# expansion.net
KiCad netlist of a schematic drawn in EAGLE
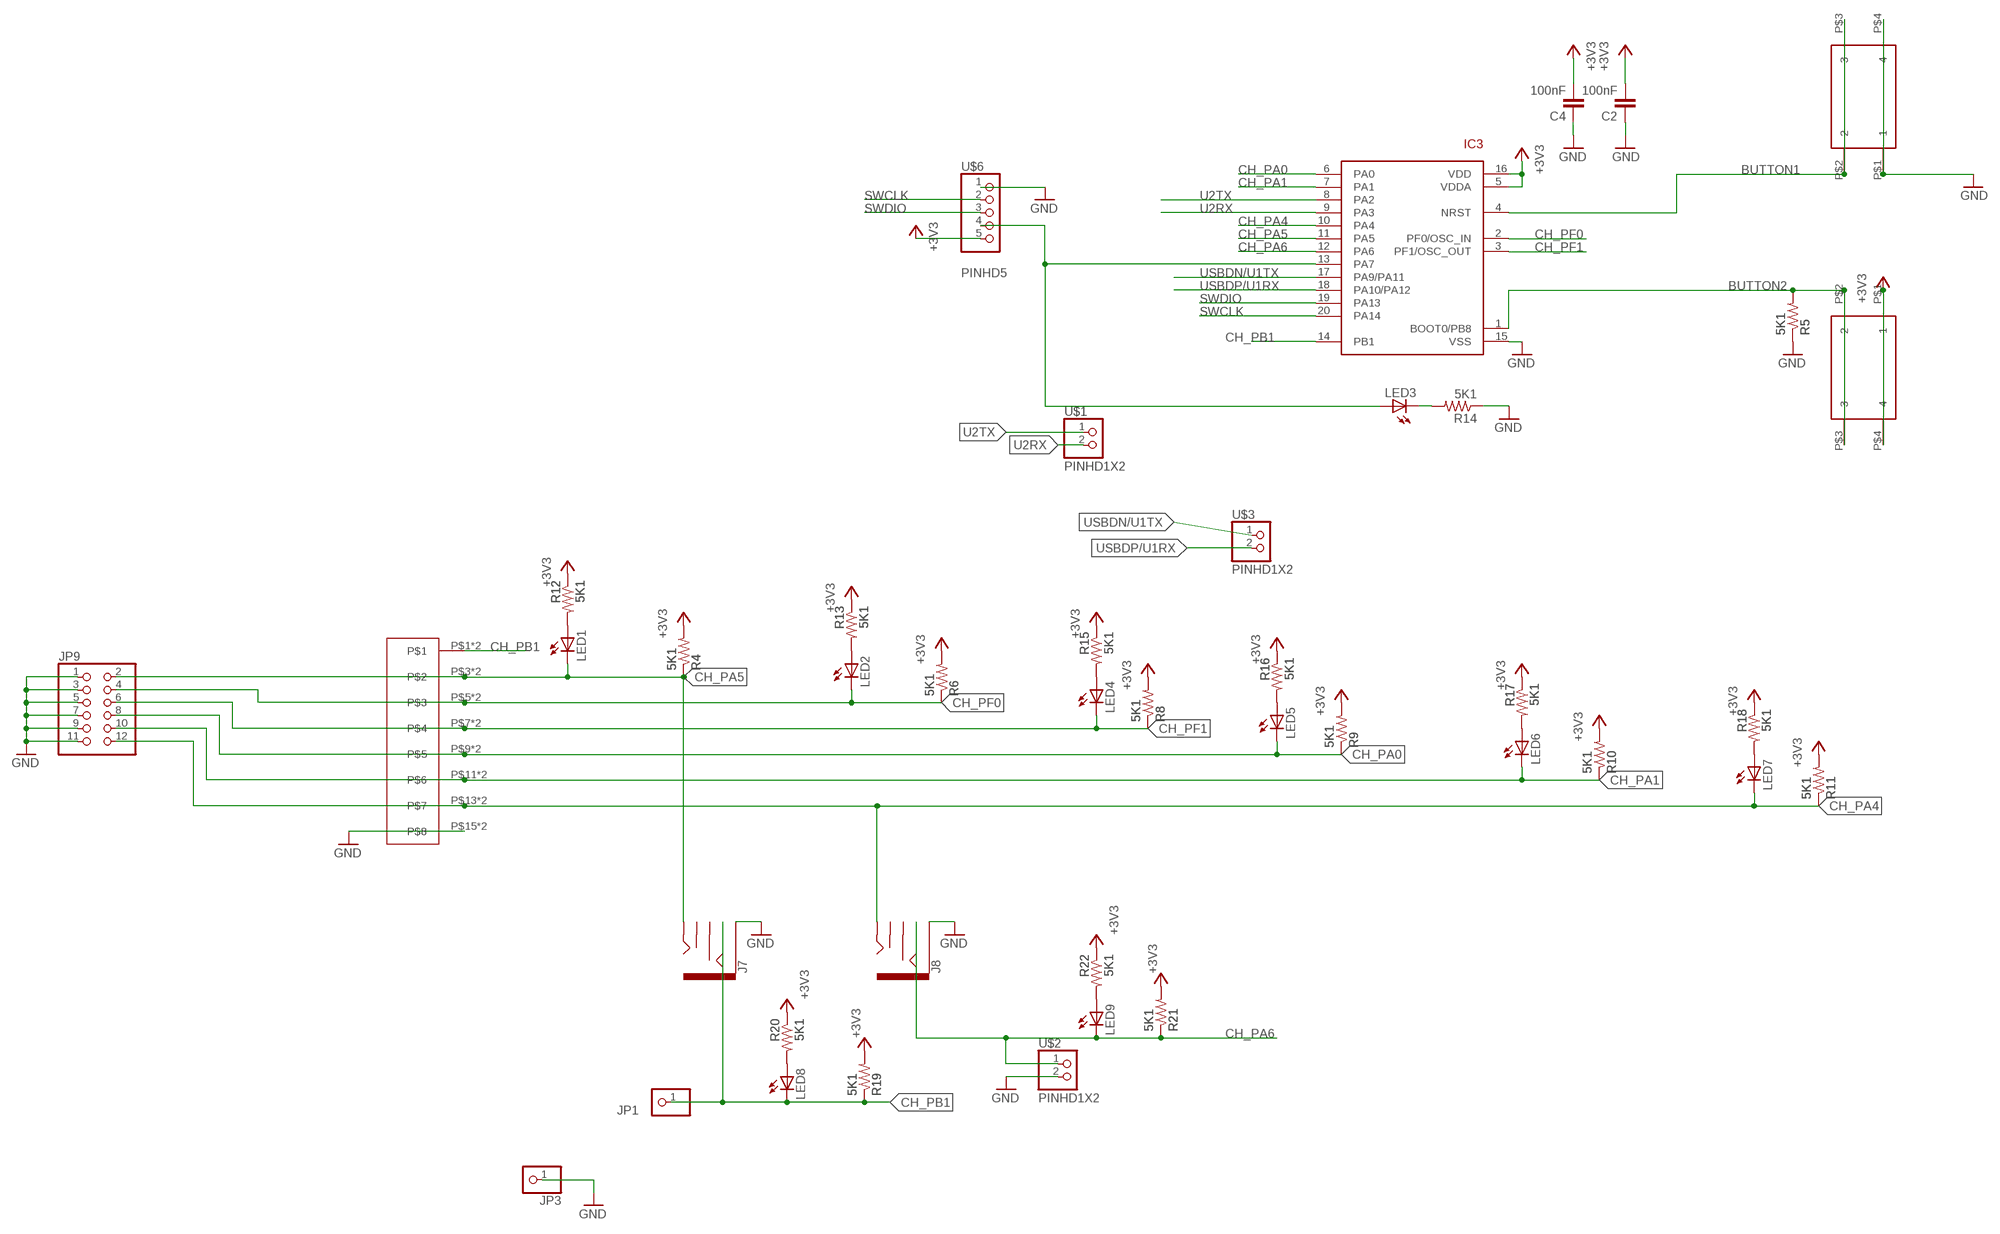
[diagram p0: schematic, sheet 1, part 1 of 2]
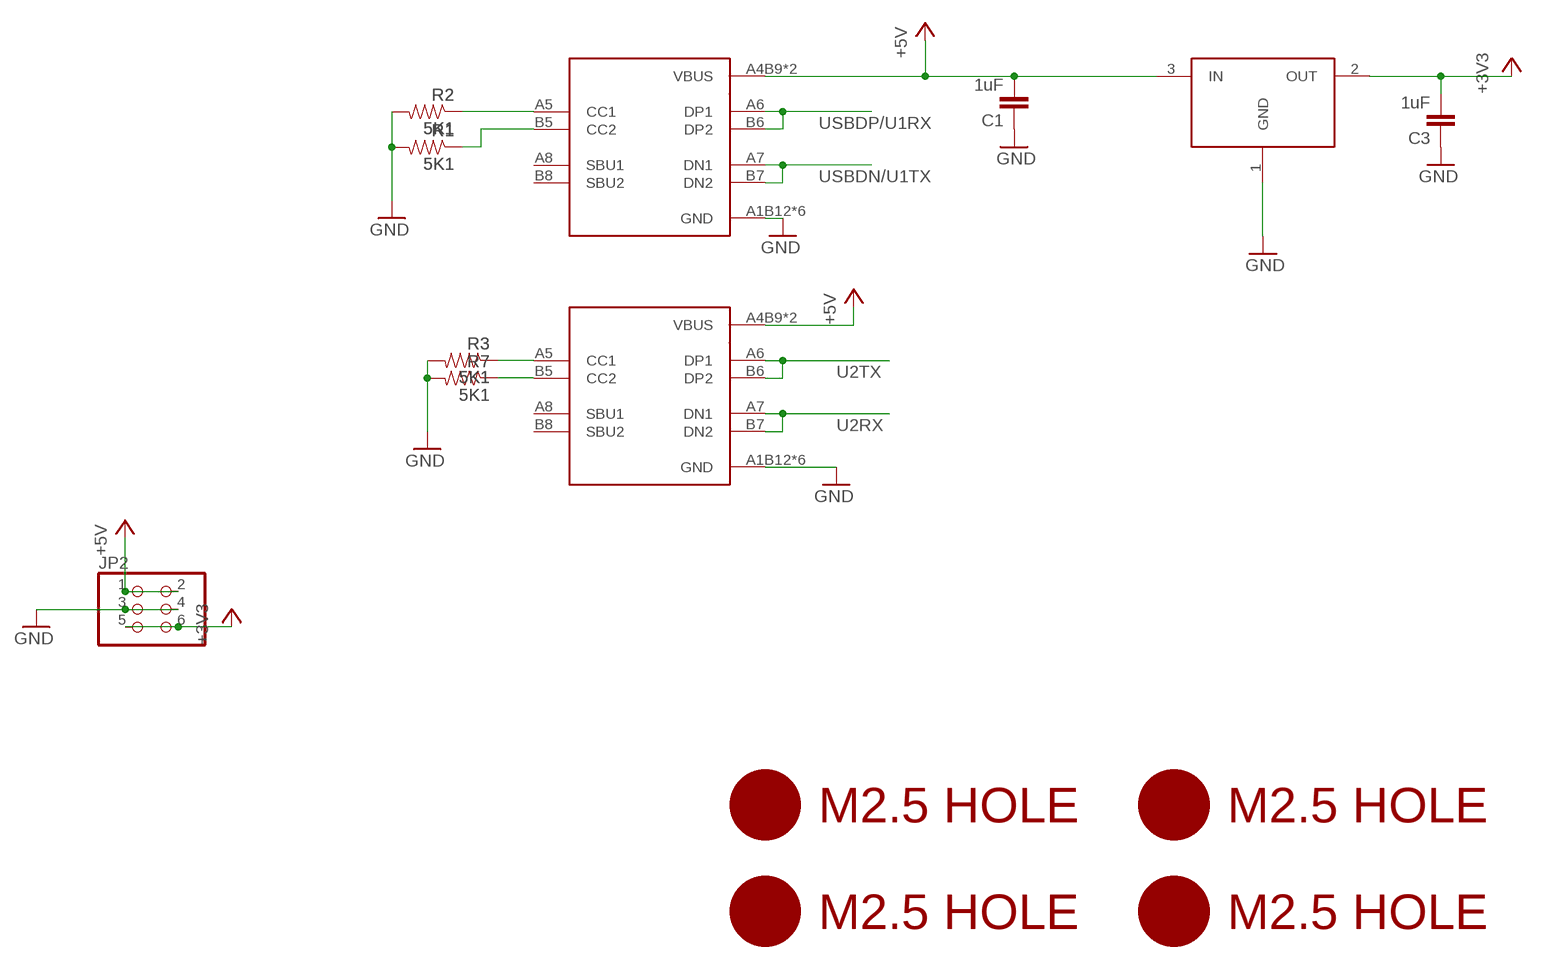
[diagram p1: schematic, sheet 1, part 2 of 2]

(export (version "E")
  (design (tool "Eeschema 10.0.6"))
  (components
    (comp (ref "C1")
      (value "1uF")
      (footprint "eagle-import:0805")
      (libsource (lib "eagle-import") (part "CAP0805"))
    )
    (comp (ref "C2")
      (value "100nF")
      (footprint "eagle-import:0805")
      (libsource (lib "eagle-import") (part "CAP0805"))
    )
    (comp (ref "C3")
      (value "1uF")
      (footprint "eagle-import:0805")
      (libsource (lib "eagle-import") (part "CAP0805"))
    )
    (comp (ref "C4")
      (value "100nF")
      (footprint "eagle-import:0805")
      (libsource (lib "eagle-import") (part "CAP0805"))
    )
    (comp (ref "IC3")
      (value "STM32F042F4")
      (footprint "eagle-import:TSSOP20")
      (libsource (lib "eagle-import") (part "STM32F042F4"))
    )
    (comp (ref "J7")
      (value "AUDIO_JACK_3.5MM_PTH")
      (footprint "eagle-import:AUDIO-JACK")
      (libsource (lib "eagle-import") (part "AUDIO_JACK_3.5MM_PTH"))
    )
    (comp (ref "J8")
      (value "AUDIO_JACK_3.5MM_PTH")
      (footprint "eagle-import:AUDIO-JACK")
      (libsource (lib "eagle-import") (part "AUDIO_JACK_3.5MM_PTH"))
    )
    (comp (ref "JP1")
      (value "PINHD-1X1")
      (footprint "eagle-import:1X01")
      (libsource (lib "eagle-import") (part "PINHD-1X1"))
    )
    (comp (ref "JP2")
      (value "PINHD-2X3")
      (footprint "eagle-import:2X03")
      (libsource (lib "eagle-import") (part "PINHD-2X3"))
    )
    (comp (ref "JP3")
      (value "PINHD-1X1")
      (footprint "eagle-import:1X01")
      (libsource (lib "eagle-import") (part "PINHD-1X1"))
    )
    (comp (ref "JP9")
      (value "PINHD-2X6")
      (footprint "eagle-import:2X06")
      (libsource (lib "eagle-import") (part "PINHD-2X6"))
    )
    (comp (ref "LED1")
      (value "LEDCHIP-LED0805")
      (footprint "eagle-import:CHIP-LED0805")
      (libsource (lib "eagle-import") (part "LEDCHIP-LED0805"))
    )
    (comp (ref "LED2")
      (value "LEDCHIP-LED0805")
      (footprint "eagle-import:CHIP-LED0805")
      (libsource (lib "eagle-import") (part "LEDCHIP-LED0805"))
    )
    (comp (ref "LED3")
      (value "LEDCHIP-LED0805")
      (footprint "eagle-import:CHIP-LED0805")
      (libsource (lib "eagle-import") (part "LEDCHIP-LED0805"))
    )
    (comp (ref "LED4")
      (value "LEDCHIP-LED0805")
      (footprint "eagle-import:CHIP-LED0805")
      (libsource (lib "eagle-import") (part "LEDCHIP-LED0805"))
    )
    (comp (ref "LED5")
      (value "LEDCHIP-LED0805")
      (footprint "eagle-import:CHIP-LED0805")
      (libsource (lib "eagle-import") (part "LEDCHIP-LED0805"))
    )
    (comp (ref "LED6")
      (value "LEDCHIP-LED0805")
      (footprint "eagle-import:CHIP-LED0805")
      (libsource (lib "eagle-import") (part "LEDCHIP-LED0805"))
    )
    (comp (ref "LED7")
      (value "LEDCHIP-LED0805")
      (footprint "eagle-import:CHIP-LED0805")
      (libsource (lib "eagle-import") (part "LEDCHIP-LED0805"))
    )
    (comp (ref "LED8")
      (value "LEDCHIP-LED0805")
      (footprint "eagle-import:CHIP-LED0805")
      (libsource (lib "eagle-import") (part "LEDCHIP-LED0805"))
    )
    (comp (ref "LED9")
      (value "LEDCHIP-LED0805")
      (footprint "eagle-import:CHIP-LED0805")
      (libsource (lib "eagle-import") (part "LEDCHIP-LED0805"))
    )
    (comp (ref "R1")
      (value "5K1")
      (footprint "eagle-import:0805")
      (libsource (lib "eagle-import") (part "joyAnalog_RESISTOR0805-RES"))
    )
    (comp (ref "R2")
      (value "5K1")
      (footprint "eagle-import:0805")
      (libsource (lib "eagle-import") (part "joyAnalog_RESISTOR0805-RES"))
    )
    (comp (ref "R3")
      (value "5K1")
      (footprint "eagle-import:0805")
      (libsource (lib "eagle-import") (part "joyAnalog_RESISTOR0805-RES"))
    )
    (comp (ref "R4")
      (value "5K1")
      (footprint "eagle-import:0805")
      (libsource (lib "eagle-import") (part "joyAnalog_RESISTOR0805-RES"))
    )
    (comp (ref "R5")
      (value "5K1")
      (footprint "eagle-import:0805")
      (libsource (lib "eagle-import") (part "joyAnalog_RESISTOR0805-RES"))
    )
    (comp (ref "R6")
      (value "5K1")
      (footprint "eagle-import:0805")
      (libsource (lib "eagle-import") (part "joyAnalog_RESISTOR0805-RES"))
    )
    (comp (ref "R7")
      (value "5K1")
      (footprint "eagle-import:0805")
      (libsource (lib "eagle-import") (part "joyAnalog_RESISTOR0805-RES"))
    )
    (comp (ref "R8")
      (value "5K1")
      (footprint "eagle-import:0805")
      (libsource (lib "eagle-import") (part "joyAnalog_RESISTOR0805-RES"))
    )
    (comp (ref "R9")
      (value "5K1")
      (footprint "eagle-import:0805")
      (libsource (lib "eagle-import") (part "joyAnalog_RESISTOR0805-RES"))
    )
    (comp (ref "R10")
      (value "5K1")
      (footprint "eagle-import:0805")
      (libsource (lib "eagle-import") (part "joyAnalog_RESISTOR0805-RES"))
    )
    (comp (ref "R11")
      (value "5K1")
      (footprint "eagle-import:0805")
      (libsource (lib "eagle-import") (part "joyAnalog_RESISTOR0805-RES"))
    )
    (comp (ref "R12")
      (value "5K1")
      (footprint "eagle-import:0805")
      (libsource (lib "eagle-import") (part "joyAnalog_RESISTOR0805-RES"))
    )
    (comp (ref "R13")
      (value "5K1")
      (footprint "eagle-import:0805")
      (libsource (lib "eagle-import") (part "joyAnalog_RESISTOR0805-RES"))
    )
    (comp (ref "R14")
      (value "5K1")
      (footprint "eagle-import:0805")
      (libsource (lib "eagle-import") (part "RESISTOR0805-RES"))
    )
    (comp (ref "R15")
      (value "5K1")
      (footprint "eagle-import:0805")
      (libsource (lib "eagle-import") (part "joyAnalog_RESISTOR0805-RES"))
    )
    (comp (ref "R16")
      (value "5K1")
      (footprint "eagle-import:0805")
      (libsource (lib "eagle-import") (part "joyAnalog_RESISTOR0805-RES"))
    )
    (comp (ref "R17")
      (value "5K1")
      (footprint "eagle-import:0805")
      (libsource (lib "eagle-import") (part "joyAnalog_RESISTOR0805-RES"))
    )
    (comp (ref "R18")
      (value "5K1")
      (footprint "eagle-import:0805")
      (libsource (lib "eagle-import") (part "joyAnalog_RESISTOR0805-RES"))
    )
    (comp (ref "R19")
      (value "5K1")
      (footprint "eagle-import:0805")
      (libsource (lib "eagle-import") (part "joyAnalog_RESISTOR0805-RES"))
    )
    (comp (ref "R20")
      (value "5K1")
      (footprint "eagle-import:0805")
      (libsource (lib "eagle-import") (part "joyAnalog_RESISTOR0805-RES"))
    )
    (comp (ref "R21")
      (value "5K1")
      (footprint "eagle-import:0805")
      (libsource (lib "eagle-import") (part "joyAnalog_RESISTOR0805-RES"))
    )
    (comp (ref "R22")
      (value "5K1")
      (footprint "eagle-import:0805")
      (libsource (lib "eagle-import") (part "joyAnalog_RESISTOR0805-RES"))
    )
    (comp (ref "SW3")
      (value "324_SW")
      (footprint "eagle-import:342_SWICH_FOOT")
      (libsource (lib "eagle-import") (part "324_SW"))
    )
    (comp (ref "SW4")
      (value "324_SW")
      (footprint "eagle-import:342_SWICH_FOOT")
      (libsource (lib "eagle-import") (part "324_SW"))
    )
    (comp (ref "U$1")
      (value "PINHD1X2")
      (footprint "eagle-import:1X02")
      (libsource (lib "eagle-import") (part "PINHD1X2"))
    )
    (comp (ref "U$2")
      (value "PINHD1X2")
      (footprint "eagle-import:1X02")
      (libsource (lib "eagle-import") (part "PINHD1X2"))
    )
    (comp (ref "U$3")
      (value "PINHD1X2")
      (footprint "eagle-import:1X02")
      (libsource (lib "eagle-import") (part "PINHD1X2"))
    )
    (comp (ref "U$6")
      (value "PINHD5")
      (footprint "eagle-import:1X05")
      (libsource (lib "eagle-import") (part "PINHD5"))
    )
    (comp (ref "U$8")
      (value "M2.5HOLE")
      (footprint "eagle-import:M2.5HOLE")
      (libsource (lib "eagle-import") (part "M2.5HOLE"))
    )
    (comp (ref "U$9")
      (value "M2.5HOLE")
      (footprint "eagle-import:M2.5HOLE")
      (libsource (lib "eagle-import") (part "M2.5HOLE"))
    )
    (comp (ref "U$10")
      (value "M2.5HOLE")
      (footprint "eagle-import:M2.5HOLE")
      (libsource (lib "eagle-import") (part "M2.5HOLE"))
    )
    (comp (ref "U$11")
      (value "M2.5HOLE")
      (footprint "eagle-import:M2.5HOLE")
      (libsource (lib "eagle-import") (part "M2.5HOLE"))
    )
    (comp (ref "U$14")
      (value "DG2204R-5.0-8DG2204-8")
      (footprint "eagle-import:DG2204R-8")
      (libsource (lib "eagle-import") (part "DG2204R-5.0-8DG2204-8"))
    )
    (comp (ref "U1")
      (value "USBC_16P")
      (footprint "eagle-import:USBC_16P_FOOT")
      (libsource (lib "eagle-import") (part "USBC_16P"))
    )
    (comp (ref "U2")
      (value "USBC_16P")
      (footprint "eagle-import:USBC_16P_FOOT")
      (libsource (lib "eagle-import") (part "USBC_16P"))
    )
    (comp (ref "U4")
      (value "XC6206_DEV")
      (footprint "eagle-import:SOT23R_INFINEON")
      (libsource (lib "eagle-import") (part "XC6206_DEV"))
    )
  )
  (nets
    (net (code "1") (name "+3V3") (class "Default")
      (node (ref "C2") (pin "2") (pinfunction "2_2") (pintype "passive"))
      (node (ref "C3") (pin "2") (pinfunction "2_2") (pintype "passive"))
      (node (ref "C4") (pin "2") (pinfunction "2_2") (pintype "passive"))
      (node (ref "IC3") (pin "16") (pinfunction "VDD_16") (pintype "bidirectional"))
      (node (ref "IC3") (pin "5") (pinfunction "VDDA_5") (pintype "bidirectional"))
      (node (ref "JP2") (pin "5") (pinfunction "5_5") (pintype "passive"))
      (node (ref "JP2") (pin "6") (pinfunction "6_6") (pintype "passive"))
      (node (ref "R10") (pin "2") (pinfunction "2_2") (pintype "passive"))
      (node (ref "R11") (pin "2") (pinfunction "2_2") (pintype "passive"))
      (node (ref "R12") (pin "1") (pinfunction "1_1") (pintype "passive"))
      (node (ref "R13") (pin "1") (pinfunction "1_1") (pintype "passive"))
      (node (ref "R15") (pin "1") (pinfunction "1_1") (pintype "passive"))
      (node (ref "R16") (pin "1") (pinfunction "1_1") (pintype "passive"))
      (node (ref "R17") (pin "1") (pinfunction "1_1") (pintype "passive"))
      (node (ref "R18") (pin "1") (pinfunction "1_1") (pintype "passive"))
      (node (ref "R19") (pin "2") (pinfunction "2_2") (pintype "passive"))
      (node (ref "R20") (pin "1") (pinfunction "1_1") (pintype "passive"))
      (node (ref "R21") (pin "2") (pinfunction "2_2") (pintype "passive"))
      (node (ref "R22") (pin "1") (pinfunction "1_1") (pintype "passive"))
      (node (ref "R4") (pin "2") (pinfunction "2_2") (pintype "passive"))
      (node (ref "R6") (pin "2") (pinfunction "2_2") (pintype "passive"))
      (node (ref "R8") (pin "2") (pinfunction "2_2") (pintype "passive"))
      (node (ref "R9") (pin "2") (pinfunction "2_2") (pintype "passive"))
      (node (ref "SW4") (pin "P$1") (pinfunction "1_P$1") (pintype "bidirectional"))
      (node (ref "SW4") (pin "P$4") (pinfunction "4_P$4") (pintype "bidirectional"))
      (node (ref "U$6") (pin "5") (pinfunction "5_5") (pintype "passive"))
      (node (ref "U4") (pin "2") (pinfunction "OUT_2") (pintype "bidirectional"))
    )
    (net (code "2") (name "+5V") (class "Default")
      (node (ref "C1") (pin "2") (pinfunction "2_2") (pintype "passive"))
      (node (ref "JP2") (pin "1") (pinfunction "1_1") (pintype "passive"))
      (node (ref "JP2") (pin "2") (pinfunction "2_2") (pintype "passive"))
      (node (ref "U1") (pin "A4B9") (pinfunction "VBUS_A4B9") (pintype "bidirectional"))
      (node (ref "U1") (pin "B4A9") (pinfunction "VBUS_B4A9") (pintype "bidirectional"))
      (node (ref "U2") (pin "A4B9") (pinfunction "VBUS_A4B9") (pintype "bidirectional"))
      (node (ref "U2") (pin "B4A9") (pinfunction "VBUS_B4A9") (pintype "bidirectional"))
      (node (ref "U4") (pin "3") (pinfunction "IN_3") (pintype "bidirectional"))
    )
    (net (code "3") (name "/BUTTON1") (class "Default")
      (node (ref "IC3") (pin "4") (pinfunction "NRST_4") (pintype "bidirectional"))
      (node (ref "SW3") (pin "P$2") (pinfunction "2_P$2") (pintype "bidirectional"))
      (node (ref "SW3") (pin "P$3") (pinfunction "3_P$3") (pintype "bidirectional"))
    )
    (net (code "4") (name "/BUTTON2") (class "Default")
      (node (ref "IC3") (pin "1") (pinfunction "BOOT0/PB8_1") (pintype "bidirectional"))
      (node (ref "R5") (pin "2") (pinfunction "2_2") (pintype "passive"))
      (node (ref "SW4") (pin "P$2") (pinfunction "2_P$2") (pintype "bidirectional"))
      (node (ref "SW4") (pin "P$3") (pinfunction "3_P$3") (pintype "bidirectional"))
    )
    (net (code "5") (name "/CH_PA6") (class "Default")
      (node (ref "IC3") (pin "12") (pinfunction "PA6_12") (pintype "bidirectional"))
      (node (ref "J8") (pin "RING") (pinfunction "RING_RING") (pintype "bidirectional"))
      (node (ref "LED9") (pin "C") (pinfunction "C_C") (pintype "passive"))
      (node (ref "R21") (pin "1") (pinfunction "1_1") (pintype "passive"))
      (node (ref "U$2") (pin "1") (pinfunction "1_1") (pintype "passive"))
    )
    (net (code "6") (name "/SWCLK") (class "Default")
      (node (ref "IC3") (pin "20") (pinfunction "PA14_20") (pintype "bidirectional"))
      (node (ref "U$6") (pin "2") (pinfunction "2_2") (pintype "passive"))
    )
    (net (code "7") (name "/SWDIO") (class "Default")
      (node (ref "IC3") (pin "19") (pinfunction "PA13_19") (pintype "bidirectional"))
      (node (ref "U$6") (pin "3") (pinfunction "3_3") (pintype "passive"))
    )
    (net (code "8") (name "CH_PA0") (class "Default")
      (node (ref "IC3") (pin "6") (pinfunction "PA0_6") (pintype "bidirectional"))
      (node (ref "JP9") (pin "8") (pinfunction "8_8") (pintype "passive"))
      (node (ref "LED5") (pin "C") (pinfunction "C_C") (pintype "passive"))
      (node (ref "R9") (pin "1") (pinfunction "1_1") (pintype "passive"))
      (node (ref "U$14") (pin "P$10") (pinfunction "P$5_P$10") (pintype "bidirectional"))
      (node (ref "U$14") (pin "P$9") (pinfunction "P$5_P$9") (pintype "bidirectional"))
    )
    (net (code "9") (name "CH_PA1") (class "Default")
      (node (ref "IC3") (pin "7") (pinfunction "PA1_7") (pintype "bidirectional"))
      (node (ref "JP9") (pin "10") (pinfunction "10_10") (pintype "passive"))
      (node (ref "LED6") (pin "C") (pinfunction "C_C") (pintype "passive"))
      (node (ref "R10") (pin "1") (pinfunction "1_1") (pintype "passive"))
      (node (ref "U$14") (pin "P$11") (pinfunction "P$6_P$11") (pintype "bidirectional"))
      (node (ref "U$14") (pin "P$12") (pinfunction "P$6_P$12") (pintype "bidirectional"))
    )
    (net (code "10") (name "CH_PA4") (class "Default")
      (node (ref "IC3") (pin "10") (pinfunction "PA4_10") (pintype "bidirectional"))
      (node (ref "J8") (pin "TIP") (pinfunction "TIP_TIP") (pintype "bidirectional"))
      (node (ref "JP9") (pin "12") (pinfunction "12_12") (pintype "passive"))
      (node (ref "LED7") (pin "C") (pinfunction "C_C") (pintype "passive"))
      (node (ref "R11") (pin "1") (pinfunction "1_1") (pintype "passive"))
      (node (ref "U$14") (pin "P$13") (pinfunction "P$7_P$13") (pintype "bidirectional"))
      (node (ref "U$14") (pin "P$14") (pinfunction "P$7_P$14") (pintype "bidirectional"))
    )
    (net (code "11") (name "CH_PA5") (class "Default")
      (node (ref "IC3") (pin "11") (pinfunction "PA5_11") (pintype "bidirectional"))
      (node (ref "J7") (pin "TIP") (pinfunction "TIP_TIP") (pintype "bidirectional"))
      (node (ref "JP9") (pin "2") (pinfunction "2_2") (pintype "passive"))
      (node (ref "LED1") (pin "C") (pinfunction "C_C") (pintype "passive"))
      (node (ref "R4") (pin "1") (pinfunction "1_1") (pintype "passive"))
      (node (ref "U$14") (pin "P$3") (pinfunction "P$2_P$3") (pintype "bidirectional"))
      (node (ref "U$14") (pin "P$4") (pinfunction "P$2_P$4") (pintype "bidirectional"))
    )
    (net (code "12") (name "CH_PB1") (class "Default")
      (node (ref "IC3") (pin "14") (pinfunction "PB1_14") (pintype "bidirectional"))
      (node (ref "J7") (pin "RING") (pinfunction "RING_RING") (pintype "bidirectional"))
      (node (ref "JP1") (pin "1") (pinfunction "1_1") (pintype "passive"))
      (node (ref "LED8") (pin "C") (pinfunction "C_C") (pintype "passive"))
      (node (ref "R19") (pin "1") (pinfunction "1_1") (pintype "passive"))
      (node (ref "U$14") (pin "P$1") (pinfunction "P$1_P$1") (pintype "bidirectional"))
      (node (ref "U$14") (pin "P$2") (pinfunction "P$1_P$2") (pintype "bidirectional"))
    )
    (net (code "13") (name "CH_PF0") (class "Default")
      (node (ref "IC3") (pin "2") (pinfunction "PF0/OSC_IN_2") (pintype "bidirectional"))
      (node (ref "JP9") (pin "4") (pinfunction "4_4") (pintype "passive"))
      (node (ref "LED2") (pin "C") (pinfunction "C_C") (pintype "passive"))
      (node (ref "R6") (pin "1") (pinfunction "1_1") (pintype "passive"))
      (node (ref "U$14") (pin "P$5") (pinfunction "P$3_P$5") (pintype "bidirectional"))
      (node (ref "U$14") (pin "P$6") (pinfunction "P$3_P$6") (pintype "bidirectional"))
    )
    (net (code "14") (name "CH_PF1") (class "Default")
      (node (ref "IC3") (pin "3") (pinfunction "PF1/OSC_OUT_3") (pintype "bidirectional"))
      (node (ref "JP9") (pin "6") (pinfunction "6_6") (pintype "passive"))
      (node (ref "LED4") (pin "C") (pinfunction "C_C") (pintype "passive"))
      (node (ref "R8") (pin "1") (pinfunction "1_1") (pintype "passive"))
      (node (ref "U$14") (pin "P$7") (pinfunction "P$4_P$7") (pintype "bidirectional"))
      (node (ref "U$14") (pin "P$8") (pinfunction "P$4_P$8") (pintype "bidirectional"))
    )
    (net (code "15") (name "GND") (class "Default")
      (node (ref "C1") (pin "1") (pinfunction "1_1") (pintype "passive"))
      (node (ref "C2") (pin "1") (pinfunction "1_1") (pintype "passive"))
      (node (ref "C3") (pin "1") (pinfunction "1_1") (pintype "passive"))
      (node (ref "C4") (pin "1") (pinfunction "1_1") (pintype "passive"))
      (node (ref "IC3") (pin "15") (pinfunction "VSS_15") (pintype "bidirectional"))
      (node (ref "J7") (pin "SLEEVE") (pinfunction "SLEEVE_SLEEVE") (pintype "bidirectional"))
      (node (ref "J8") (pin "SLEEVE") (pinfunction "SLEEVE_SLEEVE") (pintype "bidirectional"))
      (node (ref "JP2") (pin "3") (pinfunction "3_3") (pintype "passive"))
      (node (ref "JP2") (pin "4") (pinfunction "4_4") (pintype "passive"))
      (node (ref "JP3") (pin "1") (pinfunction "1_1") (pintype "passive"))
      (node (ref "JP9") (pin "1") (pinfunction "1_1") (pintype "passive"))
      (node (ref "JP9") (pin "11") (pinfunction "11_11") (pintype "passive"))
      (node (ref "JP9") (pin "3") (pinfunction "3_3") (pintype "passive"))
      (node (ref "JP9") (pin "5") (pinfunction "5_5") (pintype "passive"))
      (node (ref "JP9") (pin "7") (pinfunction "7_7") (pintype "passive"))
      (node (ref "JP9") (pin "9") (pinfunction "9_9") (pintype "passive"))
      (node (ref "R1") (pin "2") (pinfunction "2_2") (pintype "passive"))
      (node (ref "R14") (pin "1") (pinfunction "1_1") (pintype "passive"))
      (node (ref "R2") (pin "2") (pinfunction "2_2") (pintype "passive"))
      (node (ref "R3") (pin "2") (pinfunction "2_2") (pintype "passive"))
      (node (ref "R5") (pin "1") (pinfunction "1_1") (pintype "passive"))
      (node (ref "R7") (pin "2") (pinfunction "2_2") (pintype "passive"))
      (node (ref "SW3") (pin "P$1") (pinfunction "1_P$1") (pintype "bidirectional"))
      (node (ref "SW3") (pin "P$4") (pinfunction "4_P$4") (pintype "bidirectional"))
      (node (ref "U$14") (pin "P$15") (pinfunction "P$8_P$15") (pintype "bidirectional"))
      (node (ref "U$14") (pin "P$16") (pinfunction "P$8_P$16") (pintype "bidirectional"))
      (node (ref "U$2") (pin "2") (pinfunction "2_2") (pintype "passive"))
      (node (ref "U$6") (pin "1") (pinfunction "1_1") (pintype "passive"))
      (node (ref "U1") (pin "A1B12") (pinfunction "GND_A1B12") (pintype "bidirectional"))
      (node (ref "U1") (pin "B11A12") (pinfunction "GND_B11A12") (pintype "bidirectional"))
      (node (ref "U1") (pin "P$13") (pinfunction "GND_P$13") (pintype "bidirectional"))
      (node (ref "U1") (pin "P$14") (pinfunction "GND_P$14") (pintype "bidirectional"))
      (node (ref "U1") (pin "P$15") (pinfunction "GND_P$15") (pintype "bidirectional"))
      (node (ref "U1") (pin "P$16") (pinfunction "GND_P$16") (pintype "bidirectional"))
      (node (ref "U2") (pin "A1B12") (pinfunction "GND_A1B12") (pintype "bidirectional"))
      (node (ref "U2") (pin "B11A12") (pinfunction "GND_B11A12") (pintype "bidirectional"))
      (node (ref "U2") (pin "P$13") (pinfunction "GND_P$13") (pintype "bidirectional"))
      (node (ref "U2") (pin "P$14") (pinfunction "GND_P$14") (pintype "bidirectional"))
      (node (ref "U2") (pin "P$15") (pinfunction "GND_P$15") (pintype "bidirectional"))
      (node (ref "U2") (pin "P$16") (pinfunction "GND_P$16") (pintype "bidirectional"))
      (node (ref "U4") (pin "1") (pinfunction "GND_1") (pintype "bidirectional"))
    )
    (net (code "16") (name "Net-(IC3-PA7)") (class "Default")
      (node (ref "IC3") (pin "13") (pinfunction "PA7_13") (pintype "bidirectional"))
      (node (ref "LED3") (pin "A") (pinfunction "A_A") (pintype "passive"))
      (node (ref "U$6") (pin "4") (pinfunction "4_4") (pintype "passive"))
    )
    (net (code "17") (name "Net-(LED1-PadA)") (class "Default")
      (node (ref "LED1") (pin "A") (pinfunction "A_A") (pintype "passive"))
      (node (ref "R12") (pin "2") (pinfunction "2_2") (pintype "passive"))
    )
    (net (code "18") (name "Net-(LED2-PadA)") (class "Default")
      (node (ref "LED2") (pin "A") (pinfunction "A_A") (pintype "passive"))
      (node (ref "R13") (pin "2") (pinfunction "2_2") (pintype "passive"))
    )
    (net (code "19") (name "Net-(LED3-PadC)") (class "Default")
      (node (ref "LED3") (pin "C") (pinfunction "C_C") (pintype "passive"))
      (node (ref "R14") (pin "2") (pinfunction "2_2") (pintype "passive"))
    )
    (net (code "20") (name "Net-(LED4-PadA)") (class "Default")
      (node (ref "LED4") (pin "A") (pinfunction "A_A") (pintype "passive"))
      (node (ref "R15") (pin "2") (pinfunction "2_2") (pintype "passive"))
    )
    (net (code "21") (name "Net-(LED5-PadA)") (class "Default")
      (node (ref "LED5") (pin "A") (pinfunction "A_A") (pintype "passive"))
      (node (ref "R16") (pin "2") (pinfunction "2_2") (pintype "passive"))
    )
    (net (code "22") (name "Net-(LED6-PadA)") (class "Default")
      (node (ref "LED6") (pin "A") (pinfunction "A_A") (pintype "passive"))
      (node (ref "R17") (pin "2") (pinfunction "2_2") (pintype "passive"))
    )
    (net (code "23") (name "Net-(LED7-PadA)") (class "Default")
      (node (ref "LED7") (pin "A") (pinfunction "A_A") (pintype "passive"))
      (node (ref "R18") (pin "2") (pinfunction "2_2") (pintype "passive"))
    )
    (net (code "24") (name "Net-(LED8-PadA)") (class "Default")
      (node (ref "LED8") (pin "A") (pinfunction "A_A") (pintype "passive"))
      (node (ref "R20") (pin "2") (pinfunction "2_2") (pintype "passive"))
    )
    (net (code "25") (name "Net-(LED9-PadA)") (class "Default")
      (node (ref "LED9") (pin "A") (pinfunction "A_A") (pintype "passive"))
      (node (ref "R22") (pin "2") (pinfunction "2_2") (pintype "passive"))
    )
    (net (code "26") (name "Net-(U1-CC1)") (class "Default")
      (node (ref "R3") (pin "1") (pinfunction "1_1") (pintype "passive"))
      (node (ref "U1") (pin "A5") (pinfunction "CC1_A5") (pintype "bidirectional"))
    )
    (net (code "27") (name "Net-(U1-CC2)") (class "Default")
      (node (ref "R7") (pin "1") (pinfunction "1_1") (pintype "passive"))
      (node (ref "U1") (pin "B5") (pinfunction "CC2_B5") (pintype "bidirectional"))
    )
    (net (code "28") (name "Net-(U2-CC1)") (class "Default")
      (node (ref "R2") (pin "1") (pinfunction "1_1") (pintype "passive"))
      (node (ref "U2") (pin "A5") (pinfunction "CC1_A5") (pintype "bidirectional"))
    )
    (net (code "29") (name "Net-(U2-CC2)") (class "Default")
      (node (ref "R1") (pin "1") (pinfunction "1_1") (pintype "passive"))
      (node (ref "U2") (pin "B5") (pinfunction "CC2_B5") (pintype "bidirectional"))
    )
    (net (code "30") (name "U2RX") (class "Default")
      (node (ref "IC3") (pin "9") (pinfunction "PA3_9") (pintype "bidirectional"))
      (node (ref "U$1") (pin "2") (pinfunction "2_2") (pintype "passive"))
      (node (ref "U1") (pin "A7") (pinfunction "DN1_A7") (pintype "bidirectional"))
      (node (ref "U1") (pin "B7") (pinfunction "DN2_B7") (pintype "bidirectional"))
    )
    (net (code "31") (name "U2TX") (class "Default")
      (node (ref "IC3") (pin "8") (pinfunction "PA2_8") (pintype "bidirectional"))
      (node (ref "U$1") (pin "1") (pinfunction "1_1") (pintype "passive"))
      (node (ref "U1") (pin "A6") (pinfunction "DP1_A6") (pintype "bidirectional"))
      (node (ref "U1") (pin "B6") (pinfunction "DP2_B6") (pintype "bidirectional"))
    )
    (net (code "32") (name "USBDN{slash}U1TX") (class "Default")
      (node (ref "IC3") (pin "17") (pinfunction "PA9/PA11_17") (pintype "bidirectional"))
      (node (ref "U$3") (pin "1") (pinfunction "1_1") (pintype "passive"))
      (node (ref "U2") (pin "A7") (pinfunction "DN1_A7") (pintype "bidirectional"))
      (node (ref "U2") (pin "B7") (pinfunction "DN2_B7") (pintype "bidirectional"))
    )
    (net (code "33") (name "USBDP{slash}U1RX") (class "Default")
      (node (ref "IC3") (pin "18") (pinfunction "PA10/PA12_18") (pintype "bidirectional"))
      (node (ref "U$3") (pin "2") (pinfunction "2_2") (pintype "passive"))
      (node (ref "U2") (pin "A6") (pinfunction "DP1_A6") (pintype "bidirectional"))
      (node (ref "U2") (pin "B6") (pinfunction "DP2_B6") (pintype "bidirectional"))
    )
    (net (code "34") (name "unconnected-(J7-PadRSH)") (class "Default")
      (node (ref "J7") (pin "RSH") (pinfunction "RSH_RSH") (pintype "bidirectional"))
    )
    (net (code "35") (name "unconnected-(J7-PadTSH)") (class "Default")
      (node (ref "J7") (pin "TSH") (pinfunction "TSH_TSH") (pintype "bidirectional"))
    )
    (net (code "36") (name "unconnected-(J8-PadRSH)") (class "Default")
      (node (ref "J8") (pin "RSH") (pinfunction "RSH_RSH") (pintype "bidirectional"))
    )
    (net (code "37") (name "unconnected-(J8-PadTSH)") (class "Default")
      (node (ref "J8") (pin "TSH") (pinfunction "TSH_TSH") (pintype "bidirectional"))
    )
    (net (code "38") (name "unconnected-(U1-SBU1-PadA8)") (class "Default")
      (node (ref "U1") (pin "A8") (pinfunction "SBU1_A8") (pintype "bidirectional"))
    )
    (net (code "39") (name "unconnected-(U1-SBU2-PadB8)") (class "Default")
      (node (ref "U1") (pin "B8") (pinfunction "SBU2_B8") (pintype "bidirectional"))
    )
    (net (code "40") (name "unconnected-(U2-SBU1-PadA8)") (class "Default")
      (node (ref "U2") (pin "A8") (pinfunction "SBU1_A8") (pintype "bidirectional"))
    )
    (net (code "41") (name "unconnected-(U2-SBU2-PadB8)") (class "Default")
      (node (ref "U2") (pin "B8") (pinfunction "SBU2_B8") (pintype "bidirectional"))
    )
  )
)
